# FiltrosGyrator_SCH.net
KiCad netlist of a schematic drawn in Altium Designer
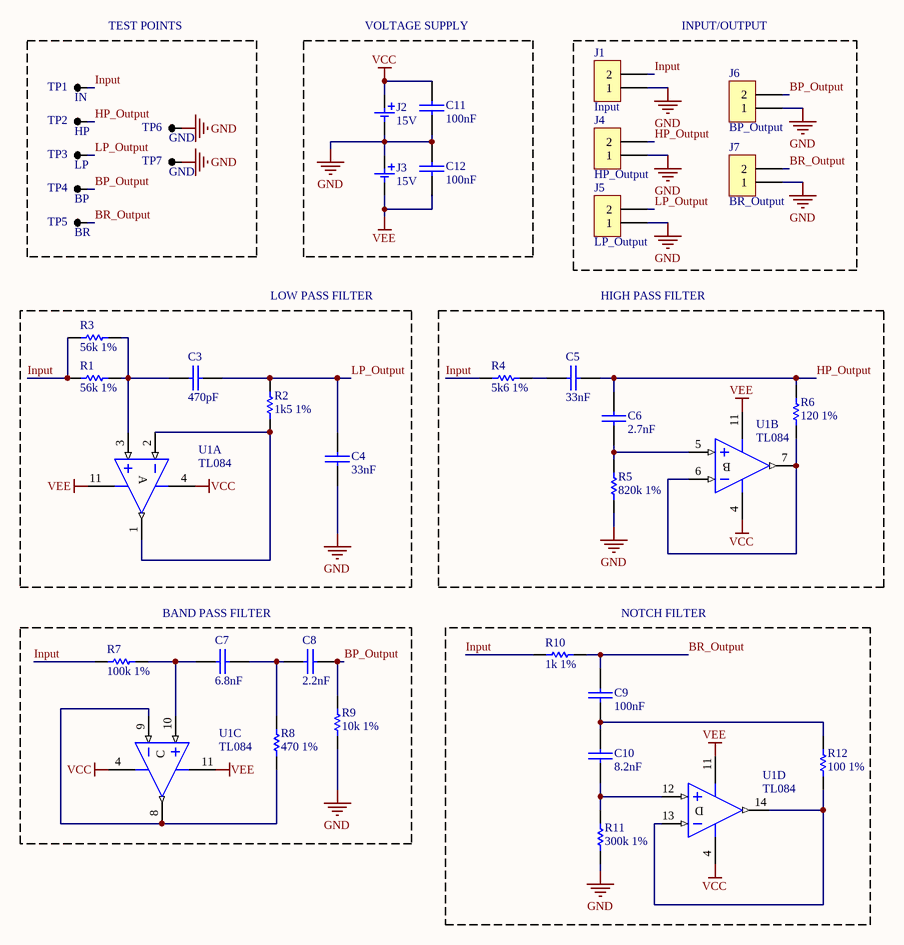
[diagram p0: FiltrosGyrator_SCH.SchDoc]

(export (version "E")
  (design (tool "Eeschema 10.0.6"))
  (components
    (comp (ref "C3") (value "470pF") (footprint "0805") (libsource (lib "LIBEBAL") (part "CAP")))
    (comp (ref "C4") (value "33nF") (footprint "0805") (libsource (lib "LIBEBAL") (part "CAP")))
    (comp (ref "C5") (value "33nF") (footprint "0805") (libsource (lib "LIBEBAL") (part "CAP")))
    (comp (ref "C6") (value "2.7nF") (footprint "0805") (libsource (lib "LIBEBAL") (part "CAP")))
    (comp (ref "C7") (value "6.8nF") (footprint "0805") (libsource (lib "LIBEBAL") (part "CAP")))
    (comp (ref "C8") (value "2.2nF") (footprint "0805") (libsource (lib "LIBEBAL") (part "CAP")))
    (comp (ref "C9") (value "100nF") (footprint "0805") (libsource (lib "LIBEBAL") (part "CAP")))
    (comp (ref "C10") (value "8.2nF") (footprint "0805") (libsource (lib "LIBEBAL") (part "CAP")))
    (comp (ref "C11") (value "100nF") (footprint "0805") (libsource (lib "LIBEBAL") (part "CAP")))
    (comp (ref "C12") (value "100nF") (footprint "0805") (libsource (lib "LIBEBAL") (part "CAP")))
    (comp (ref "J1") (value "Input") (footprint "BORNERA2") (libsource (lib "LIB PIO IX") (part "BORNERA 2")))
    (comp (ref "J2")
      (value "15V")
      (footprint "BORNERA2")
      (description "BATERIA")
      (libsource (lib "LIBEBAL") (part "BATERIA"))
    )
    (comp (ref "J3")
      (value "15V")
      (footprint "BORNERA2")
      (description "BATERIA")
      (libsource (lib "LIBEBAL") (part "BATERIA"))
    )
    (comp (ref "J4")
      (value "HP_Output")
      (footprint "BORNERA2")
      (libsource (lib "LIB PIO IX") (part "BORNERA 2"))
    )
    (comp (ref "J5")
      (value "LP_Output")
      (footprint "BORNERA2")
      (libsource (lib "LIB PIO IX") (part "BORNERA 2"))
    )
    (comp (ref "J6")
      (value "BP_Output")
      (footprint "BORNERA2")
      (libsource (lib "LIB PIO IX") (part "BORNERA 2"))
    )
    (comp (ref "J7")
      (value "BR_Output")
      (footprint "BORNERA2")
      (libsource (lib "LIB PIO IX") (part "BORNERA 2"))
    )
    (comp (ref "R1") (value "56k 1%") (footprint "0805") (libsource (lib "LIBEBAL") (part "RES")))
    (comp (ref "R2") (value "1k5 1%") (footprint "0805") (libsource (lib "LIBEBAL") (part "RES")))
    (comp (ref "R3") (value "56k 1%") (footprint "0805") (libsource (lib "LIBEBAL") (part "RES")))
    (comp (ref "R4") (value "5k6 1%") (footprint "0805") (libsource (lib "LIBEBAL") (part "RES")))
    (comp (ref "R5") (value "820k 1%") (footprint "0805") (libsource (lib "LIBEBAL") (part "RES")))
    (comp (ref "R6") (value "120 1%") (footprint "0805") (libsource (lib "LIBEBAL") (part "RES")))
    (comp (ref "R7") (value "100k 1%") (footprint "0805") (libsource (lib "LIBEBAL") (part "RES")))
    (comp (ref "R8") (value "470 1%") (footprint "0805") (libsource (lib "LIBEBAL") (part "RES")))
    (comp (ref "R9") (value "10k 1%") (footprint "0805") (libsource (lib "LIBEBAL") (part "RES")))
    (comp (ref "R10") (value "1k 1%") (footprint "0805") (libsource (lib "LIBEBAL") (part "RES")))
    (comp (ref "R11") (value "300k 1%") (footprint "0805") (libsource (lib "LIBEBAL") (part "RES")))
    (comp (ref "R12") (value "100 1%") (footprint "0805") (libsource (lib "LIBEBAL") (part "RES")))
    (comp (ref "TP1") (value "IN") (footprint "TPTH") (libsource (lib "LIBEBAL") (part "TP")))
    (comp (ref "TP2") (value "HP") (footprint "TPTH") (libsource (lib "LIBEBAL") (part "TP")))
    (comp (ref "TP3") (value "LP") (footprint "TPTH") (libsource (lib "LIBEBAL") (part "TP")))
    (comp (ref "TP4") (value "BP") (footprint "TPTH") (libsource (lib "LIBEBAL") (part "TP")))
    (comp (ref "TP5") (value "BR") (footprint "TPTH") (libsource (lib "LIBEBAL") (part "TP")))
    (comp (ref "TP6") (value "GND") (footprint "TPTH") (libsource (lib "LIBEBAL") (part "TP")))
    (comp (ref "TP7") (value "GND") (footprint "TPTH") (libsource (lib "LIBEBAL") (part "TP")))
    (comp (ref "U1")
      (value "TL084")
      (footprint "J014")
      (description "JFET-Input Operational Amplifier")
      (fields (field (name "PUBLISHER") "Altium Limited"))
      (libsource (lib "FiltrosGyrator") (part "TL084J"))
    )
  )
  (nets
    (net (code "1") (name "/BP_Output") (class "Default")
      (node (ref "C8") (pin "2") (pinfunction "2_2") (pintype "passive"))
      (node (ref "J6") (pin "2") (pinfunction "2_2") (pintype "passive"))
      (node (ref "R9") (pin "2") (pinfunction "2_2") (pintype "passive"))
      (node (ref "TP4") (pin "1") (pinfunction "1_1") (pintype "passive"))
    )
    (net (code "2") (name "/BR_Output") (class "Default")
      (node (ref "C9") (pin "1") (pinfunction "1_1") (pintype "passive"))
      (node (ref "J7") (pin "2") (pinfunction "2_2") (pintype "passive"))
      (node (ref "R10") (pin "2") (pinfunction "2_2") (pintype "passive"))
      (node (ref "TP5") (pin "1") (pinfunction "1_1") (pintype "passive"))
    )
    (net (code "3") (name "/HP_Output") (class "Default")
      (node (ref "C5") (pin "2") (pinfunction "2_2") (pintype "passive"))
      (node (ref "C6") (pin "1") (pinfunction "1_1") (pintype "passive"))
      (node (ref "J4") (pin "2") (pinfunction "2_2") (pintype "passive"))
      (node (ref "R6") (pin "1") (pinfunction "1_1") (pintype "passive"))
      (node (ref "TP2") (pin "1") (pinfunction "1_1") (pintype "passive"))
    )
    (net (code "4") (name "/Input") (class "Default")
      (node (ref "J1") (pin "2") (pinfunction "2_2") (pintype "passive"))
      (node (ref "R1") (pin "1") (pinfunction "1_1") (pintype "passive"))
      (node (ref "R10") (pin "1") (pinfunction "1_1") (pintype "passive"))
      (node (ref "R3") (pin "1") (pinfunction "1_1") (pintype "passive"))
      (node (ref "R4") (pin "1") (pinfunction "1_1") (pintype "passive"))
      (node (ref "R7") (pin "1") (pinfunction "1_1") (pintype "passive"))
      (node (ref "TP1") (pin "1") (pinfunction "1_1") (pintype "passive"))
    )
    (net (code "5") (name "/LP_Output") (class "Default")
      (node (ref "C3") (pin "2") (pinfunction "2_2") (pintype "passive"))
      (node (ref "C4") (pin "2") (pinfunction "2_2") (pintype "passive"))
      (node (ref "J5") (pin "2") (pinfunction "2_2") (pintype "passive"))
      (node (ref "R2") (pin "2") (pinfunction "2_2") (pintype "passive"))
      (node (ref "TP3") (pin "1") (pinfunction "1_1") (pintype "passive"))
    )
    (net (code "6") (name "GND") (class "Default")
      (node (ref "C11") (pin "2") (pinfunction "2_2") (pintype "passive"))
      (node (ref "C12") (pin "1") (pinfunction "1_1") (pintype "passive"))
      (node (ref "C4") (pin "1") (pinfunction "1_1") (pintype "passive"))
      (node (ref "J1") (pin "1") (pinfunction "1_1") (pintype "passive"))
      (node (ref "J2") (pin "2") (pintype "passive"))
      (node (ref "J3") (pin "1") (pintype "passive"))
      (node (ref "J4") (pin "1") (pinfunction "1_1") (pintype "passive"))
      (node (ref "J5") (pin "1") (pinfunction "1_1") (pintype "passive"))
      (node (ref "J6") (pin "1") (pinfunction "1_1") (pintype "passive"))
      (node (ref "J7") (pin "1") (pinfunction "1_1") (pintype "passive"))
      (node (ref "R11") (pin "2") (pinfunction "2_2") (pintype "passive"))
      (node (ref "R5") (pin "1") (pinfunction "1_1") (pintype "passive"))
      (node (ref "R9") (pin "1") (pinfunction "1_1") (pintype "passive"))
      (node (ref "TP6") (pin "1") (pinfunction "1_1") (pintype "passive"))
      (node (ref "TP7") (pin "1") (pinfunction "1_1") (pintype "passive"))
    )
    (net (code "7") (name "Net-(C5-Pad1)") (class "Default")
      (node (ref "C5") (pin "1") (pinfunction "1_1") (pintype "passive"))
      (node (ref "R4") (pin "2") (pinfunction "2_2") (pintype "passive"))
    )
    (net (code "8") (name "Net-(C7-Pad2)") (class "Default")
      (node (ref "C7") (pin "2") (pinfunction "2_2") (pintype "passive"))
      (node (ref "C8") (pin "1") (pinfunction "1_1") (pintype "passive"))
      (node (ref "R8") (pin "2") (pinfunction "2_2") (pintype "passive"))
    )
    (net (code "9") (name "Net-(C10-Pad2)") (class "Default")
      (node (ref "C10") (pin "2") (pinfunction "2_2") (pintype "passive"))
      (node (ref "C9") (pin "2") (pinfunction "2_2") (pintype "passive"))
      (node (ref "R12") (pin "2") (pinfunction "2_2") (pintype "passive"))
    )
    (net (code "10") (name "Net-(U1A-IN+)") (class "Default")
      (node (ref "C3") (pin "1") (pinfunction "1_1") (pintype "passive"))
      (node (ref "R1") (pin "2") (pinfunction "2_2") (pintype "passive"))
      (node (ref "R3") (pin "2") (pinfunction "2_2") (pintype "passive"))
      (node (ref "U1") (pin "3") (pinfunction "IN+_3") (pintype "input"))
    )
    (net (code "11") (name "Net-(U1A-IN-)") (class "Default")
      (node (ref "R2") (pin "1") (pinfunction "1_1") (pintype "passive"))
      (node (ref "U1") (pin "1") (pinfunction "OUT_1") (pintype "output"))
      (node (ref "U1") (pin "2") (pinfunction "IN-_2") (pintype "input"))
    )
    (net (code "12") (name "Net-(U1B-IN+)") (class "Default")
      (node (ref "C6") (pin "2") (pinfunction "2_2") (pintype "passive"))
      (node (ref "R5") (pin "2") (pinfunction "2_2") (pintype "passive"))
      (node (ref "U1") (pin "5") (pinfunction "IN+_5") (pintype "input"))
    )
    (net (code "13") (name "Net-(U1B-IN-)") (class "Default")
      (node (ref "R6") (pin "2") (pinfunction "2_2") (pintype "passive"))
      (node (ref "U1") (pin "6") (pinfunction "IN-_6") (pintype "input"))
      (node (ref "U1") (pin "7") (pinfunction "OUT_7") (pintype "output"))
    )
    (net (code "14") (name "Net-(U1C-IN+)") (class "Default")
      (node (ref "C7") (pin "1") (pinfunction "1_1") (pintype "passive"))
      (node (ref "R7") (pin "2") (pinfunction "2_2") (pintype "passive"))
      (node (ref "U1") (pin "10") (pinfunction "IN+_10") (pintype "input"))
    )
    (net (code "15") (name "Net-(U1C-IN-)") (class "Default")
      (node (ref "R8") (pin "1") (pinfunction "1_1") (pintype "passive"))
      (node (ref "U1") (pin "8") (pinfunction "OUT_8") (pintype "output"))
      (node (ref "U1") (pin "9") (pinfunction "IN-_9") (pintype "input"))
    )
    (net (code "16") (name "Net-(U1D-IN+)") (class "Default")
      (node (ref "C10") (pin "1") (pinfunction "1_1") (pintype "passive"))
      (node (ref "R11") (pin "1") (pinfunction "1_1") (pintype "passive"))
      (node (ref "U1") (pin "12") (pinfunction "IN+_12") (pintype "input"))
    )
    (net (code "17") (name "Net-(U1D-IN-)") (class "Default")
      (node (ref "R12") (pin "1") (pinfunction "1_1") (pintype "passive"))
      (node (ref "U1") (pin "13") (pinfunction "IN-_13") (pintype "input"))
      (node (ref "U1") (pin "14") (pinfunction "OUT_14") (pintype "output"))
    )
    (net (code "18") (name "VCC") (class "Default")
      (node (ref "C11") (pin "1") (pinfunction "1_1") (pintype "passive"))
      (node (ref "J2") (pin "1") (pintype "passive"))
      (node (ref "U1") (pin "4") (pinfunction "V+_4") (pintype "power_in"))
    )
    (net (code "19") (name "VEE") (class "Default")
      (node (ref "C12") (pin "2") (pinfunction "2_2") (pintype "passive"))
      (node (ref "J3") (pin "2") (pintype "passive"))
      (node (ref "U1") (pin "11") (pinfunction "V-_11") (pintype "power_in"))
    )
  )
)
